# Fonte.net
KiCad netlist of a schematic drawn in Altium Designer
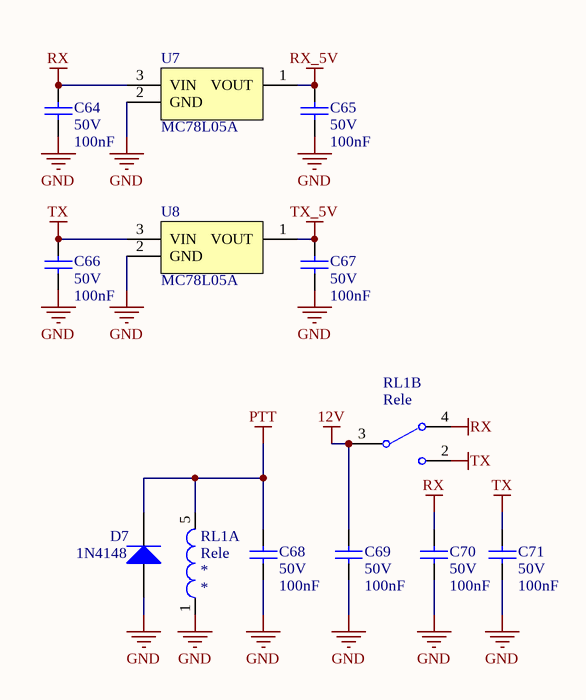
[diagram p0: Fonte.SchDoc]

(export (version "E")
  (design (tool "Eeschema 10.0.6"))
  (components
    (comp (ref "C64")
      (value "100nF")
      (footprint "CC0603")
      (description "Capacitor (Semiconductor SIM Model)")
      (fields (field (name "TENSÃO") "50V") (field (name "Comment") "Capacitor Cerâmico"))
      (libsource (lib "NavarroCAP") (part "Cap 100nF 50V 0603 X7R"))
    )
    (comp (ref "C65")
      (value "100nF")
      (footprint "CC0603")
      (description "Capacitor (Semiconductor SIM Model)")
      (fields (field (name "TENSÃO") "50V") (field (name "Comment") "Capacitor Cerâmico"))
      (libsource (lib "NavarroCAP") (part "Cap 100nF 50V 0603 X7R"))
    )
    (comp (ref "C66")
      (value "100nF")
      (footprint "CC0603")
      (description "Capacitor (Semiconductor SIM Model)")
      (fields (field (name "TENSÃO") "50V") (field (name "Comment") "Capacitor Cerâmico"))
      (libsource (lib "NavarroCAP") (part "Cap 100nF 50V 0603 X7R"))
    )
    (comp (ref "C67")
      (value "100nF")
      (footprint "CC0603")
      (description "Capacitor (Semiconductor SIM Model)")
      (fields (field (name "TENSÃO") "50V") (field (name "Comment") "Capacitor Cerâmico"))
      (libsource (lib "NavarroCAP") (part "Cap 100nF 50V 0603 X7R"))
    )
    (comp (ref "C68")
      (value "100nF")
      (footprint "CC0603")
      (description "Capacitor (Semiconductor SIM Model)")
      (fields (field (name "TENSÃO") "50V") (field (name "Comment") "Capacitor Cerâmico"))
      (libsource (lib "NavarroCAP") (part "Cap 100nF 50V 0603 X7R"))
    )
    (comp (ref "C69")
      (value "100nF")
      (footprint "CC0603")
      (description "Capacitor (Semiconductor SIM Model)")
      (fields (field (name "TENSÃO") "50V") (field (name "Comment") "Capacitor Cerâmico"))
      (libsource (lib "NavarroCAP") (part "Cap 100nF 50V 0603 X7R"))
    )
    (comp (ref "C70")
      (value "100nF")
      (footprint "CC0603")
      (description "Capacitor (Semiconductor SIM Model)")
      (fields (field (name "TENSÃO") "50V") (field (name "Comment") "Capacitor Cerâmico"))
      (libsource (lib "NavarroCAP") (part "Cap 100nF 50V 0603 X7R"))
    )
    (comp (ref "C71")
      (value "100nF")
      (footprint "CC0603")
      (description "Capacitor (Semiconductor SIM Model)")
      (fields (field (name "TENSÃO") "50V") (field (name "Comment") "Capacitor Cerâmico"))
      (libsource (lib "NavarroCAP") (part "Cap 100nF 50V 0603 X7R"))
    )
    (comp (ref "D7")
      (value "1N4148")
      (footprint "SOD-323 Diodo-K2")
      (description "Small Signal Diodes")
      (libsource (lib "NavarroSEMI") (part "DP 75V 150mA SOD-323"))
    )
    (comp (ref "RL1")
      (value "Rele")
      (footprint "Rele SPDT")
      (description "Rele de uma chave e dois contatos")
      (fields (field (name "CORRENTE") "*") (field (name "TENSÃO") "*"))
      (libsource (lib "Navarro") (part "Rele SPDT"))
    )
    (comp (ref "U7")
      (value "MC78L05A")
      (footprint "SOT-89-3N")
      (description "Regulador Linear 5V")
      (libsource (lib "Navarro") (part "MC78L05"))
    )
    (comp (ref "U8")
      (value "MC78L05A")
      (footprint "SOT-89-3N")
      (description "Regulador Linear 5V")
      (libsource (lib "Navarro") (part "MC78L05"))
    )
  )
  (nets
    (net (code "1") (name "12V") (class "Default")
      (node (ref "C69") (pin "2") (pinfunction "2_2") (pintype "passive"))
      (node (ref "RL1") (pin "3") (pinfunction "C_3") (pintype "passive"))
    )
    (net (code "2") (name "GND") (class "Default")
      (node (ref "C64") (pin "1") (pinfunction "1_1") (pintype "passive"))
      (node (ref "C65") (pin "1") (pinfunction "1_1") (pintype "passive"))
      (node (ref "C66") (pin "1") (pinfunction "1_1") (pintype "passive"))
      (node (ref "C67") (pin "1") (pinfunction "1_1") (pintype "passive"))
      (node (ref "C68") (pin "1") (pinfunction "1_1") (pintype "passive"))
      (node (ref "C69") (pin "1") (pinfunction "1_1") (pintype "passive"))
      (node (ref "C70") (pin "1") (pinfunction "1_1") (pintype "passive"))
      (node (ref "C71") (pin "1") (pinfunction "1_1") (pintype "passive"))
      (node (ref "D7") (pin "1") (pinfunction "A_1") (pintype "passive"))
      (node (ref "RL1") (pin "1") (pinfunction "L1_1") (pintype "passive"))
      (node (ref "U7") (pin "2") (pinfunction "GND_2") (pintype "power_in"))
      (node (ref "U8") (pin "2") (pinfunction "GND_2") (pintype "power_in"))
    )
    (net (code "3") (name "PTT") (class "Default")
      (node (ref "C68") (pin "2") (pinfunction "2_2") (pintype "passive"))
      (node (ref "D7") (pin "2") (pinfunction "K_2") (pintype "passive"))
      (node (ref "RL1") (pin "5") (pinfunction "L2_5") (pintype "passive"))
    )
    (net (code "4") (name "RX") (class "Default")
      (node (ref "C64") (pin "2") (pinfunction "2_2") (pintype "passive"))
      (node (ref "C70") (pin "2") (pinfunction "2_2") (pintype "passive"))
      (node (ref "RL1") (pin "4") (pinfunction "NF_4") (pintype "passive"))
      (node (ref "U7") (pin "3") (pinfunction "VIN_3") (pintype "power_in"))
    )
    (net (code "5") (name "RX_5V") (class "Default")
      (node (ref "C65") (pin "2") (pinfunction "2_2") (pintype "passive"))
      (node (ref "U7") (pin "1") (pinfunction "VOUT_1") (pintype "power_in"))
    )
    (net (code "6") (name "TX") (class "Default")
      (node (ref "C66") (pin "2") (pinfunction "2_2") (pintype "passive"))
      (node (ref "C71") (pin "2") (pinfunction "2_2") (pintype "passive"))
      (node (ref "RL1") (pin "2") (pinfunction "NA_2") (pintype "passive"))
      (node (ref "U8") (pin "3") (pinfunction "VIN_3") (pintype "power_in"))
    )
    (net (code "7") (name "TX_5V") (class "Default")
      (node (ref "C67") (pin "2") (pinfunction "2_2") (pintype "passive"))
      (node (ref "U8") (pin "1") (pinfunction "VOUT_1") (pintype "power_in"))
    )
  )
)
